# 311_lora.net
KiCad netlist of a schematic drawn in EAGLE
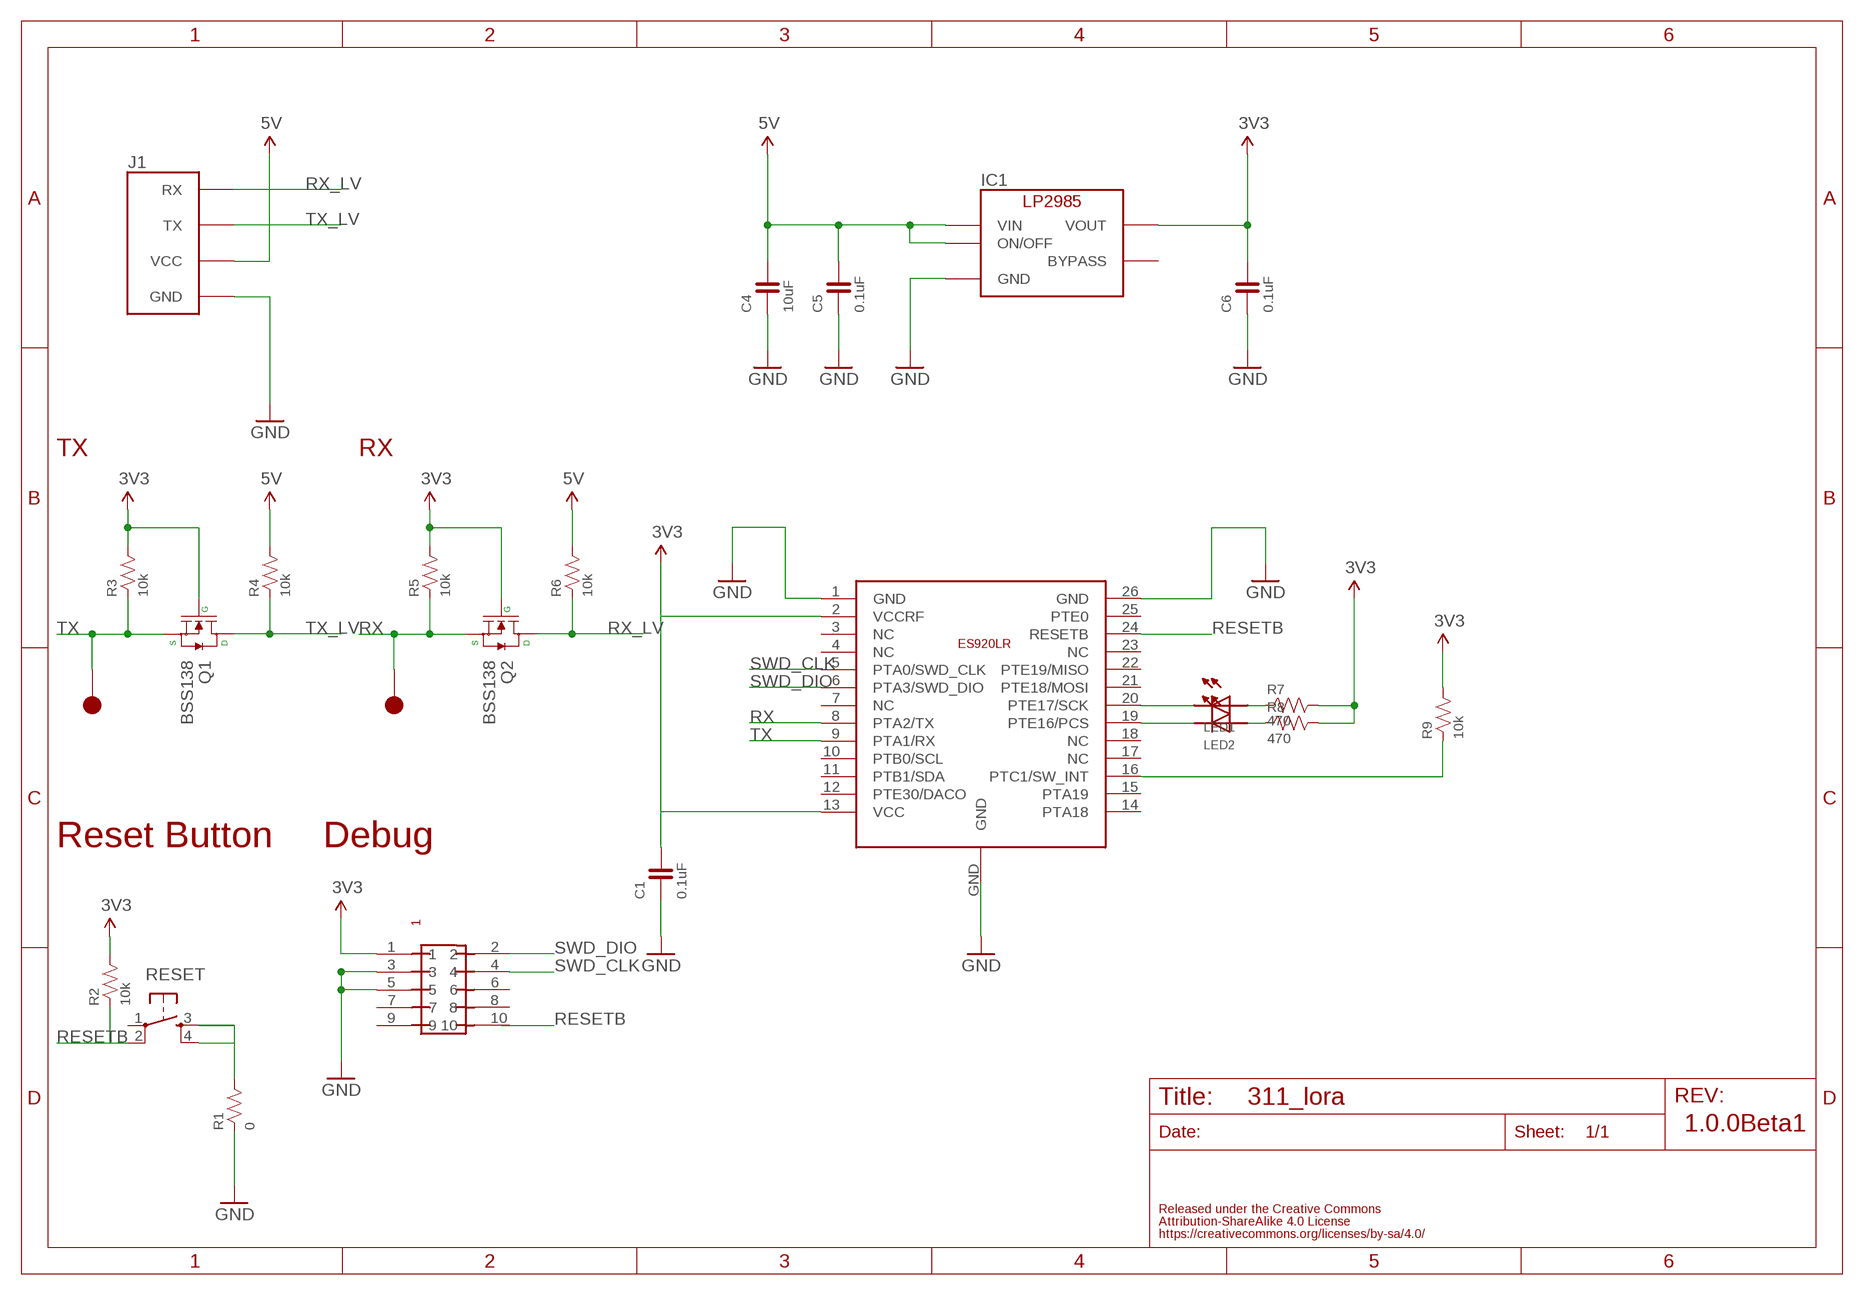
[diagram p0: schematic, sheet 1]

(export (version "E")
  (design (tool "Eeschema 10.0.6"))
  (components
    (comp (ref "C1")
      (value "0.1uF")
      (footprint "eagle-import:0603-NARROW")
      (libsource (lib "eagle-import") (part "CAPACITOR-0603_NARROW"))
    )
    (comp (ref "C4")
      (value "10uF")
      (footprint "eagle-import:0603-NARROW")
      (libsource (lib "eagle-import") (part "CAPACITOR-0603_NARROW"))
    )
    (comp (ref "C5")
      (value "0.1uF")
      (footprint "eagle-import:0603-NARROW")
      (libsource (lib "eagle-import") (part "CAPACITOR-0603_NARROW"))
    )
    (comp (ref "C6")
      (value "0.1uF")
      (footprint "eagle-import:0603-NARROW")
      (libsource (lib "eagle-import") (part "CAPACITOR-0603_NARROW"))
    )
    (comp (ref "IC1")
      (value "LP2985-33DBV")
      (footprint "eagle-import:SOT-23-5")
      (libsource (lib "eagle-import") (part "LP2985-33DBV"))
    )
    (comp (ref "J1")
      (value "FABO_BRICK_SERIAL-LONGER")
      (footprint "eagle-import:FABO_BRICK_SERIAL_LONGER")
      (libsource (lib "eagle-import") (part "FABO_BRICK_SERIAL-LONGER"))
    )
    (comp (ref "LED1")
      (value "LED-0603")
      (footprint "eagle-import:0603")
      (libsource (lib "eagle-import") (part "LED-0603"))
    )
    (comp (ref "LED2")
      (value "LED-0603")
      (footprint "eagle-import:0603")
      (libsource (lib "eagle-import") (part "LED-0603"))
    )
    (comp (ref "Q1")
      (value "BSS138")
      (footprint "eagle-import:SOT23-3")
      (libsource (lib "eagle-import") (part "MOSFET-N"))
    )
    (comp (ref "Q2")
      (value "BSS138")
      (footprint "eagle-import:SOT23-3")
      (libsource (lib "eagle-import") (part "MOSFET-N"))
    )
    (comp (ref "R1")
      (value "0")
      (footprint "eagle-import:0603-NARROW")
      (libsource (lib "eagle-import") (part "RESISTOR-0603-NARROW"))
    )
    (comp (ref "R2")
      (value "10k")
      (footprint "eagle-import:0603-NARROW")
      (libsource (lib "eagle-import") (part "RESISTOR-0603-NARROW"))
    )
    (comp (ref "R3")
      (value "10k")
      (footprint "eagle-import:0603-NARROW")
      (libsource (lib "eagle-import") (part "RESISTOR-0603-NARROW"))
    )
    (comp (ref "R4")
      (value "10k")
      (footprint "eagle-import:0603-NARROW")
      (libsource (lib "eagle-import") (part "RESISTOR-0603-NARROW"))
    )
    (comp (ref "R5")
      (value "10k")
      (footprint "eagle-import:0603-NARROW")
      (libsource (lib "eagle-import") (part "RESISTOR-0603-NARROW"))
    )
    (comp (ref "R6")
      (value "10k")
      (footprint "eagle-import:0603-NARROW")
      (libsource (lib "eagle-import") (part "RESISTOR-0603-NARROW"))
    )
    (comp (ref "R7")
      (value "470")
      (footprint "eagle-import:0603-NARROW")
      (libsource (lib "eagle-import") (part "RESISTOR-0603-NARROW"))
    )
    (comp (ref "R8")
      (value "470")
      (footprint "eagle-import:0603-NARROW")
      (libsource (lib "eagle-import") (part "RESISTOR-0603-NARROW"))
    )
    (comp (ref "R9")
      (value "10k")
      (footprint "eagle-import:0603-NARROW")
      (libsource (lib "eagle-import") (part "RESISTOR-0603-NARROW"))
    )
    (comp (ref "RESET")
      (value "TACT-SWITCH-SMD_KMR2")
      (footprint "eagle-import:KMR2")
      (libsource (lib "eagle-import") (part "TACT-SWITCH-SMD_KMR2"))
    )
    (comp (ref "TP10")
      (value "TP-15")
      (footprint "eagle-import:TP-15")
      (libsource (lib "eagle-import") (part "TP-15"))
    )
    (comp (ref "TP11")
      (value "TP-15")
      (footprint "eagle-import:TP-15")
      (libsource (lib "eagle-import") (part "TP-15"))
    )
    (comp (ref "U$2")
      (value "ES920LR")
      (footprint "eagle-import:ES920LR")
      (libsource (lib "eagle-import") (part "ES920LR"))
    )
    (comp (ref "U$8")
      (value "PIN-HEADER-SMT(1.27MM)2X5")
      (footprint "eagle-import:PIN-HEADER-SMT(1.27MM)2X5")
      (libsource (lib "eagle-import") (part "PIN-HEADER-SMT(1.27MM)2X5"))
    )
  )
  (nets
    (net (code "1") (name "/RESETB") (class "Default")
      (node (ref "R2") (pin "1") (pinfunction "1_1") (pintype "bidirectional"))
      (node (ref "RESET") (pin "2") (pinfunction "2_2") (pintype "passive"))
      (node (ref "U$2") (pin "24") (pinfunction "RESETB_24") (pintype "bidirectional"))
      (node (ref "U$8") (pin "10") (pinfunction "10_10") (pintype "bidirectional"))
    )
    (net (code "2") (name "/RX") (class "Default")
      (node (ref "Q2") (pin "2") (pinfunction "S_2") (pintype "passive"))
      (node (ref "R5") (pin "1") (pinfunction "1_1") (pintype "bidirectional"))
      (node (ref "TP10") (pin "1") (pinfunction "1_1") (pintype "bidirectional"))
      (node (ref "U$2") (pin "8") (pinfunction "PTA2/TX_8") (pintype "bidirectional"))
    )
    (net (code "3") (name "/RX_LV") (class "Default")
      (node (ref "J1") (pin "RX") (pinfunction "RX_RX") (pintype "bidirectional"))
      (node (ref "Q2") (pin "3") (pinfunction "D_3") (pintype "passive"))
      (node (ref "R6") (pin "1") (pinfunction "1_1") (pintype "bidirectional"))
    )
    (net (code "4") (name "/SWD_CLK") (class "Default")
      (node (ref "U$2") (pin "5") (pinfunction "PTA0/SWD_CLK_5") (pintype "bidirectional"))
      (node (ref "U$8") (pin "4") (pinfunction "4_4") (pintype "bidirectional"))
    )
    (net (code "5") (name "/SWD_DIO") (class "Default")
      (node (ref "U$2") (pin "6") (pinfunction "PTA3/SWD_DIO_6") (pintype "bidirectional"))
      (node (ref "U$8") (pin "2") (pinfunction "2_2") (pintype "bidirectional"))
    )
    (net (code "6") (name "/TX") (class "Default")
      (node (ref "Q1") (pin "2") (pinfunction "S_2") (pintype "passive"))
      (node (ref "R3") (pin "1") (pinfunction "1_1") (pintype "bidirectional"))
      (node (ref "TP11") (pin "1") (pinfunction "1_1") (pintype "bidirectional"))
      (node (ref "U$2") (pin "9") (pinfunction "PTA1/RX_9") (pintype "bidirectional"))
    )
    (net (code "7") (name "/TX_LV") (class "Default")
      (node (ref "J1") (pin "TX") (pinfunction "TX_TX") (pintype "bidirectional"))
      (node (ref "Q1") (pin "3") (pinfunction "D_3") (pintype "passive"))
      (node (ref "R4") (pin "1") (pinfunction "1_1") (pintype "bidirectional"))
    )
    (net (code "8") (name "3V3") (class "Default")
      (node (ref "C1") (pin "2") (pinfunction "2_2") (pintype "passive"))
      (node (ref "C6") (pin "2") (pinfunction "2_2") (pintype "passive"))
      (node (ref "IC1") (pin "5") (pinfunction "VOUT_5") (pintype "output"))
      (node (ref "Q1") (pin "1") (pinfunction "G_1") (pintype "passive"))
      (node (ref "Q2") (pin "1") (pinfunction "G_1") (pintype "passive"))
      (node (ref "R2") (pin "2") (pinfunction "2_2") (pintype "bidirectional"))
      (node (ref "R3") (pin "2") (pinfunction "2_2") (pintype "bidirectional"))
      (node (ref "R5") (pin "2") (pinfunction "2_2") (pintype "bidirectional"))
      (node (ref "R7") (pin "2") (pinfunction "2_2") (pintype "bidirectional"))
      (node (ref "R8") (pin "2") (pinfunction "2_2") (pintype "bidirectional"))
      (node (ref "R9") (pin "2") (pinfunction "2_2") (pintype "bidirectional"))
      (node (ref "U$2") (pin "13") (pinfunction "VCC_13") (pintype "bidirectional"))
      (node (ref "U$2") (pin "2") (pinfunction "VCCRF_2") (pintype "bidirectional"))
      (node (ref "U$8") (pin "1") (pinfunction "1_1") (pintype "bidirectional"))
    )
    (net (code "9") (name "5V") (class "Default")
      (node (ref "C4") (pin "2") (pinfunction "2_2") (pintype "passive"))
      (node (ref "C5") (pin "2") (pinfunction "2_2") (pintype "passive"))
      (node (ref "IC1") (pin "1") (pinfunction "VIN_1") (pintype "input"))
      (node (ref "IC1") (pin "3") (pinfunction "ON/OFF_3") (pintype "input"))
      (node (ref "J1") (pin "VCC") (pinfunction "VCC_VCC") (pintype "bidirectional"))
      (node (ref "R4") (pin "2") (pinfunction "2_2") (pintype "bidirectional"))
      (node (ref "R6") (pin "2") (pinfunction "2_2") (pintype "bidirectional"))
    )
    (net (code "10") (name "GND") (class "Default")
      (node (ref "C1") (pin "1") (pinfunction "1_1") (pintype "passive"))
      (node (ref "C4") (pin "1") (pinfunction "1_1") (pintype "passive"))
      (node (ref "C5") (pin "1") (pinfunction "1_1") (pintype "passive"))
      (node (ref "C6") (pin "1") (pinfunction "1_1") (pintype "passive"))
      (node (ref "IC1") (pin "2") (pinfunction "GND_2") (pintype "power_in"))
      (node (ref "J1") (pin "GND") (pinfunction "GND_GND") (pintype "bidirectional"))
      (node (ref "R1") (pin "1") (pinfunction "1_1") (pintype "bidirectional"))
      (node (ref "U$2") (pin "1") (pinfunction "GND_1") (pintype "bidirectional"))
      (node (ref "U$2") (pin "26") (pinfunction "GND_26") (pintype "bidirectional"))
      (node (ref "U$2") (pin "GND") (pinfunction "GND_GND") (pintype "bidirectional"))
      (node (ref "U$8") (pin "3") (pinfunction "3_3") (pintype "bidirectional"))
      (node (ref "U$8") (pin "5") (pinfunction "5_5") (pintype "bidirectional"))
    )
    (net (code "11") (name "Net-(LED1-PadANODE)") (class "Default")
      (node (ref "LED1") (pin "ANODE") (pinfunction "ANODE_ANODE") (pintype "passive"))
      (node (ref "R7") (pin "1") (pinfunction "1_1") (pintype "bidirectional"))
    )
    (net (code "12") (name "Net-(LED2-PadANODE)") (class "Default")
      (node (ref "LED2") (pin "ANODE") (pinfunction "ANODE_ANODE") (pintype "passive"))
      (node (ref "R8") (pin "1") (pinfunction "1_1") (pintype "bidirectional"))
    )
    (net (code "13") (name "Net-(R1-Pad2)") (class "Default")
      (node (ref "R1") (pin "2") (pinfunction "2_2") (pintype "bidirectional"))
      (node (ref "RESET") (pin "3") (pinfunction "3_3") (pintype "passive"))
      (node (ref "RESET") (pin "4") (pinfunction "4_4") (pintype "passive"))
    )
    (net (code "14") (name "Net-(U$2-PTC1{slash}SW_INT)") (class "Default")
      (node (ref "R9") (pin "1") (pinfunction "1_1") (pintype "bidirectional"))
      (node (ref "U$2") (pin "16") (pinfunction "PTC1/SW_INT_16") (pintype "bidirectional"))
    )
    (net (code "15") (name "Net-(U$2-PTE16{slash}PCS)") (class "Default")
      (node (ref "LED2") (pin "CATHODE") (pinfunction "CATHODE_CATHODE") (pintype "passive"))
      (node (ref "U$2") (pin "19") (pinfunction "PTE16/PCS_19") (pintype "bidirectional"))
    )
    (net (code "16") (name "Net-(U$2-PTE17{slash}SCK)") (class "Default")
      (node (ref "LED1") (pin "CATHODE") (pinfunction "CATHODE_CATHODE") (pintype "passive"))
      (node (ref "U$2") (pin "20") (pinfunction "PTE17/SCK_20") (pintype "bidirectional"))
    )
    (net (code "17") (name "unconnected-(IC1-BYPASS-Pad4)") (class "Default")
      (node (ref "IC1") (pin "4") (pinfunction "BYPASS_4") (pintype "bidirectional"))
    )
    (net (code "18") (name "unconnected-(RESET-Pad1)") (class "Default")
      (node (ref "RESET") (pin "1") (pinfunction "1_1") (pintype "passive"))
    )
    (net (code "19") (name "unconnected-(U$2-NC-Pad3)") (class "Default")
      (node (ref "U$2") (pin "3") (pinfunction "NC_3") (pintype "bidirectional"))
    )
    (net (code "20") (name "unconnected-(U$2-NC-Pad4)") (class "Default")
      (node (ref "U$2") (pin "4") (pinfunction "NC_4") (pintype "bidirectional"))
    )
    (net (code "21") (name "unconnected-(U$2-NC-Pad7)") (class "Default")
      (node (ref "U$2") (pin "7") (pinfunction "NC_7") (pintype "bidirectional"))
    )
    (net (code "22") (name "unconnected-(U$2-NC-Pad17)") (class "Default")
      (node (ref "U$2") (pin "17") (pinfunction "NC_17") (pintype "bidirectional"))
    )
    (net (code "23") (name "unconnected-(U$2-NC-Pad18)") (class "Default")
      (node (ref "U$2") (pin "18") (pinfunction "NC_18") (pintype "bidirectional"))
    )
    (net (code "24") (name "unconnected-(U$2-NC-Pad23)") (class "Default")
      (node (ref "U$2") (pin "23") (pinfunction "NC_23") (pintype "bidirectional"))
    )
    (net (code "25") (name "unconnected-(U$2-PTA18-Pad14)") (class "Default")
      (node (ref "U$2") (pin "14") (pinfunction "PTA18_14") (pintype "bidirectional"))
    )
    (net (code "26") (name "unconnected-(U$2-PTA19-Pad15)") (class "Default")
      (node (ref "U$2") (pin "15") (pinfunction "PTA19_15") (pintype "bidirectional"))
    )
    (net (code "27") (name "unconnected-(U$2-PTB0{slash}SCL-Pad10)") (class "Default")
      (node (ref "U$2") (pin "10") (pinfunction "PTB0/SCL_10") (pintype "bidirectional"))
    )
    (net (code "28") (name "unconnected-(U$2-PTB1{slash}SDA-Pad11)") (class "Default")
      (node (ref "U$2") (pin "11") (pinfunction "PTB1/SDA_11") (pintype "bidirectional"))
    )
    (net (code "29") (name "unconnected-(U$2-PTE0-Pad25)") (class "Default")
      (node (ref "U$2") (pin "25") (pinfunction "PTE0_25") (pintype "bidirectional"))
    )
    (net (code "30") (name "unconnected-(U$2-PTE18{slash}MOSI-Pad21)") (class "Default")
      (node (ref "U$2") (pin "21") (pinfunction "PTE18/MOSI_21") (pintype "bidirectional"))
    )
    (net (code "31") (name "unconnected-(U$2-PTE19{slash}MISO-Pad22)") (class "Default")
      (node (ref "U$2") (pin "22") (pinfunction "PTE19/MISO_22") (pintype "bidirectional"))
    )
    (net (code "32") (name "unconnected-(U$2-PTE30{slash}DACO-Pad12)") (class "Default")
      (node (ref "U$2") (pin "12") (pinfunction "PTE30/DACO_12") (pintype "bidirectional"))
    )
    (net (code "33") (name "unconnected-(U$8-Pad6)") (class "Default")
      (node (ref "U$8") (pin "6") (pinfunction "6_6") (pintype "bidirectional"))
    )
    (net (code "34") (name "unconnected-(U$8-Pad7)") (class "Default")
      (node (ref "U$8") (pin "7") (pinfunction "7_7") (pintype "bidirectional"))
    )
    (net (code "35") (name "unconnected-(U$8-Pad8)") (class "Default")
      (node (ref "U$8") (pin "8") (pinfunction "8_8") (pintype "bidirectional"))
    )
    (net (code "36") (name "unconnected-(U$8-Pad9)") (class "Default")
      (node (ref "U$8") (pin "9") (pinfunction "9_9") (pintype "bidirectional"))
    )
  )
)
